# SENSOR.net
KiCad netlist of a schematic drawn in Altium Designer
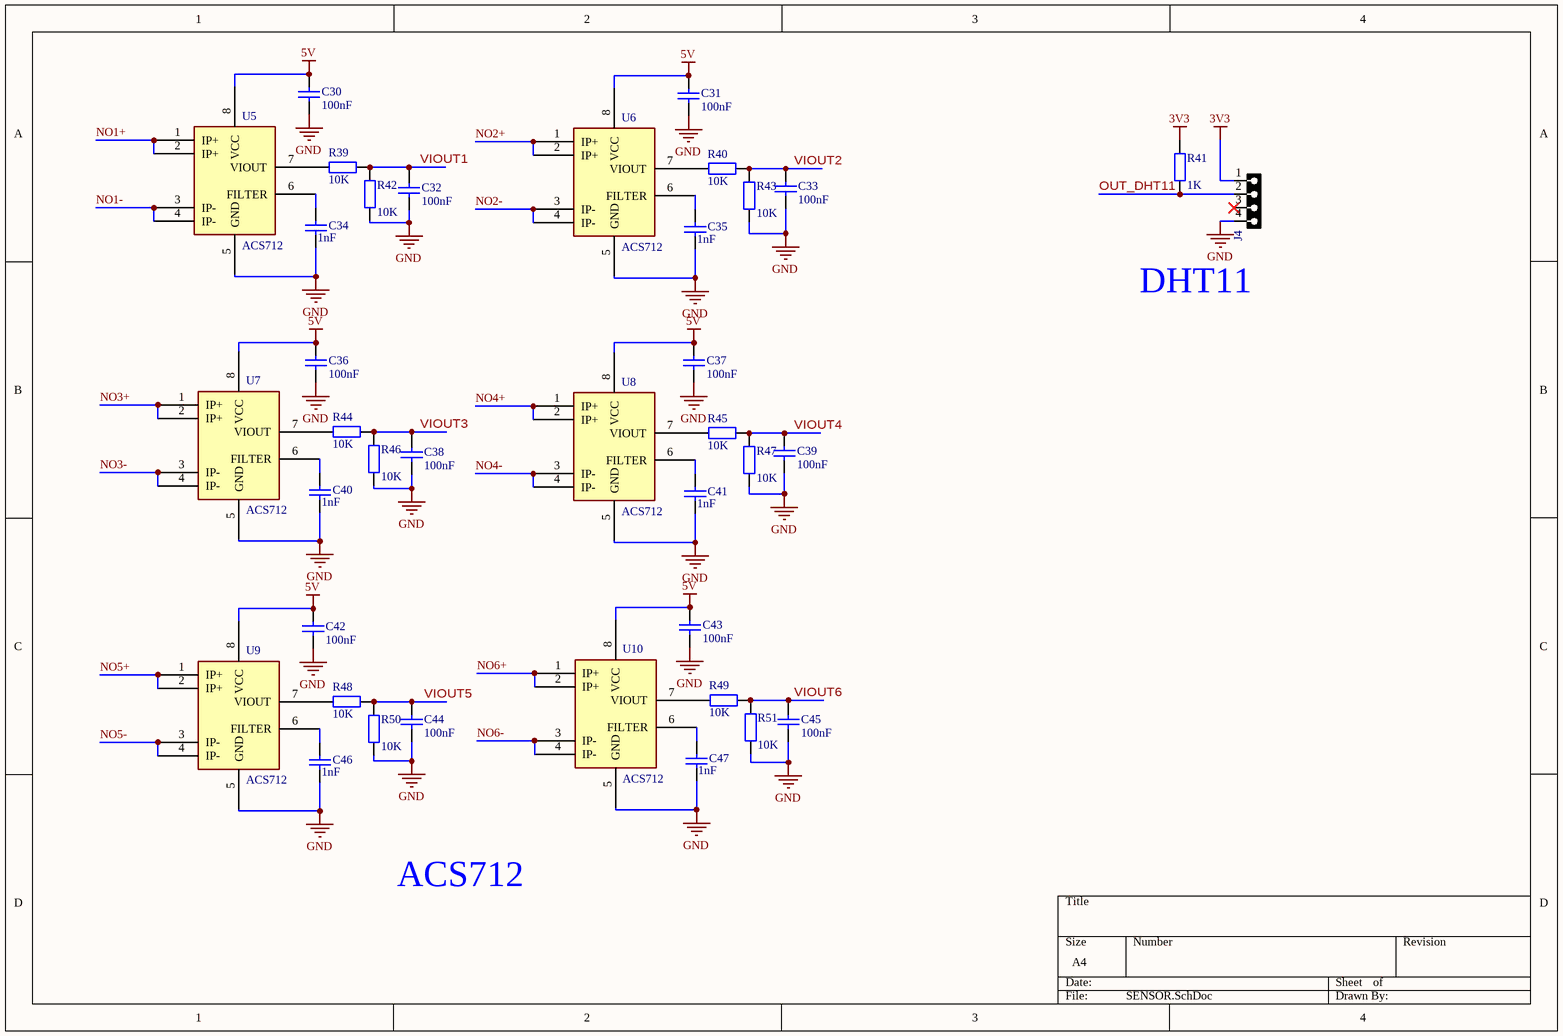
[diagram p0: SENSOR.SchDoc]

(export (version "E")
  (design (tool "Eeschema 10.0.6"))
  (components
    (comp (ref "C30")
      (value "100nF_0603_1%")
      (footprint "tu 0603")
      (description "Capacitor, Ceramic, 50V")
      (fields (field (name "MA_HANG") "100nF"))
      (libsource (lib "THU VIEN SCH") (part "Tu 0603 470pF 50V 10%"))
    )
    (comp (ref "C31")
      (value "100nF_0603_1%")
      (footprint "tu 0603")
      (description "Capacitor, Ceramic, 50V")
      (fields (field (name "MA_HANG") "100nF"))
      (libsource (lib "THU VIEN SCH") (part "Tu 0603 470pF 50V 10%"))
    )
    (comp (ref "C32")
      (value "100nF_0603_1%")
      (footprint "tu 0603")
      (description "Capacitor, Ceramic, 50V")
      (fields (field (name "MA_HANG") "100nF"))
      (libsource (lib "THU VIEN SCH") (part "Tu 0603 470pF 50V 10%"))
    )
    (comp (ref "C33")
      (value "100nF_0603_1%")
      (footprint "tu 0603")
      (description "Capacitor, Ceramic, 50V")
      (fields (field (name "MA_HANG") "100nF"))
      (libsource (lib "THU VIEN SCH") (part "Tu 0603 470pF 50V 10%"))
    )
    (comp (ref "C34")
      (value "1nF_0603_1%")
      (footprint "tu 0603")
      (description "Capacitor, Ceramic, 50V")
      (fields (field (name "MA_HANG") "1nF"))
      (libsource (lib "THU VIEN SCH") (part "Tu 0603 470pF 50V 10%"))
    )
    (comp (ref "C35")
      (value "1nF_0603_1%")
      (footprint "tu 0603")
      (description "Capacitor, Ceramic, 50V")
      (fields (field (name "MA_HANG") "1nF"))
      (libsource (lib "THU VIEN SCH") (part "Tu 0603 470pF 50V 10%"))
    )
    (comp (ref "C36")
      (value "100nF_0603_1%")
      (footprint "tu 0603")
      (description "Capacitor, Ceramic, 50V")
      (fields (field (name "MA_HANG") "100nF"))
      (libsource (lib "THU VIEN SCH") (part "Tu 0603 470pF 50V 10%"))
    )
    (comp (ref "C37")
      (value "100nF_0603_1%")
      (footprint "tu 0603")
      (description "Capacitor, Ceramic, 50V")
      (fields (field (name "MA_HANG") "100nF"))
      (libsource (lib "THU VIEN SCH") (part "Tu 0603 470pF 50V 10%"))
    )
    (comp (ref "C38")
      (value "100nF_0603_1%")
      (footprint "tu 0603")
      (description "Capacitor, Ceramic, 50V")
      (fields (field (name "MA_HANG") "100nF"))
      (libsource (lib "THU VIEN SCH") (part "Tu 0603 470pF 50V 10%"))
    )
    (comp (ref "C39")
      (value "100nF_0603_1%")
      (footprint "tu 0603")
      (description "Capacitor, Ceramic, 50V")
      (fields (field (name "MA_HANG") "100nF"))
      (libsource (lib "THU VIEN SCH") (part "Tu 0603 470pF 50V 10%"))
    )
    (comp (ref "C40")
      (value "1nF_0603_1%")
      (footprint "tu 0603")
      (description "Capacitor, Ceramic, 50V")
      (fields (field (name "MA_HANG") "1nF"))
      (libsource (lib "THU VIEN SCH") (part "Tu 0603 470pF 50V 10%"))
    )
    (comp (ref "C41")
      (value "1nF_0603_1%")
      (footprint "tu 0603")
      (description "Capacitor, Ceramic, 50V")
      (fields (field (name "MA_HANG") "1nF"))
      (libsource (lib "THU VIEN SCH") (part "Tu 0603 470pF 50V 10%"))
    )
    (comp (ref "C42")
      (value "100nF_0603_1%")
      (footprint "tu 0603")
      (description "Capacitor, Ceramic, 50V")
      (fields (field (name "MA_HANG") "100nF"))
      (libsource (lib "THU VIEN SCH") (part "Tu 0603 470pF 50V 10%"))
    )
    (comp (ref "C43")
      (value "100nF_0603_1%")
      (footprint "tu 0603")
      (description "Capacitor, Ceramic, 50V")
      (fields (field (name "MA_HANG") "100nF"))
      (libsource (lib "THU VIEN SCH") (part "Tu 0603 470pF 50V 10%"))
    )
    (comp (ref "C44")
      (value "100nF_0603_1%")
      (footprint "tu 0603")
      (description "Capacitor, Ceramic, 50V")
      (fields (field (name "MA_HANG") "100nF"))
      (libsource (lib "THU VIEN SCH") (part "Tu 0603 470pF 50V 10%"))
    )
    (comp (ref "C45")
      (value "100nF_0603_1%")
      (footprint "tu 0603")
      (description "Capacitor, Ceramic, 50V")
      (fields (field (name "MA_HANG") "100nF"))
      (libsource (lib "THU VIEN SCH") (part "Tu 0603 470pF 50V 10%"))
    )
    (comp (ref "C46")
      (value "1nF_0603_1%")
      (footprint "tu 0603")
      (description "Capacitor, Ceramic, 50V")
      (fields (field (name "MA_HANG") "1nF"))
      (libsource (lib "THU VIEN SCH") (part "Tu 0603 470pF 50V 10%"))
    )
    (comp (ref "C47")
      (value "1nF_0603_1%")
      (footprint "tu 0603")
      (description "Capacitor, Ceramic, 50V")
      (fields (field (name "MA_HANG") "1nF"))
      (libsource (lib "THU VIEN SCH") (part "Tu 0603 470pF 50V 10%"))
    )
    (comp (ref "J4")
      (value "HDRF4")
      (footprint "HDR_F_1X4")
      (description "CONN, HEADER, Female, pitch: 2.54mm, 4POS")
      (libsource (lib "AH_Library") (part "HDR_F_1X4"))
    )
    (comp (ref "R39")
      (value "10K_0603_1%")
      (footprint "tro smd 0603")
      (description "RES SMD 0603")
      (fields (field (name "MA_HANG") "10K"))
      (libsource (lib "THU VIEN SCH") (part "Tro 0603 5% 10k"))
    )
    (comp (ref "R40")
      (value "10K_0603_1%")
      (footprint "tro smd 0603")
      (description "RES SMD 0603")
      (fields (field (name "MA_HANG") "10K"))
      (libsource (lib "THU VIEN SCH") (part "Tro 0603 5% 10k"))
    )
    (comp (ref "R41")
      (value "1K_0603_1%")
      (footprint "tro smd 0603")
      (description "RES SMD 0603")
      (fields (field (name "MA_HANG") "1K"))
      (libsource (lib "THU VIEN SCH") (part "Tro 0603 5% 10k"))
    )
    (comp (ref "R42")
      (value "10K_0603_1%")
      (footprint "tro smd 0603")
      (description "RES SMD 0603")
      (fields (field (name "MA_HANG") "10K"))
      (libsource (lib "THU VIEN SCH") (part "Tro 0603 5% 10k"))
    )
    (comp (ref "R43")
      (value "10K_0603_1%")
      (footprint "tro smd 0603")
      (description "RES SMD 0603")
      (fields (field (name "MA_HANG") "10K"))
      (libsource (lib "THU VIEN SCH") (part "Tro 0603 5% 10k"))
    )
    (comp (ref "R44")
      (value "10K_0603_1%")
      (footprint "tro smd 0603")
      (description "RES SMD 0603")
      (fields (field (name "MA_HANG") "10K"))
      (libsource (lib "THU VIEN SCH") (part "Tro 0603 5% 10k"))
    )
    (comp (ref "R45")
      (value "10K_0603_1%")
      (footprint "tro smd 0603")
      (description "RES SMD 0603")
      (fields (field (name "MA_HANG") "10K"))
      (libsource (lib "THU VIEN SCH") (part "Tro 0603 5% 10k"))
    )
    (comp (ref "R46")
      (value "10K_0603_1%")
      (footprint "tro smd 0603")
      (description "RES SMD 0603")
      (fields (field (name "MA_HANG") "10K"))
      (libsource (lib "THU VIEN SCH") (part "Tro 0603 5% 10k"))
    )
    (comp (ref "R47")
      (value "10K_0603_1%")
      (footprint "tro smd 0603")
      (description "RES SMD 0603")
      (fields (field (name "MA_HANG") "10K"))
      (libsource (lib "THU VIEN SCH") (part "Tro 0603 5% 10k"))
    )
    (comp (ref "R48")
      (value "10K_0603_1%")
      (footprint "tro smd 0603")
      (description "RES SMD 0603")
      (fields (field (name "MA_HANG") "10K"))
      (libsource (lib "THU VIEN SCH") (part "Tro 0603 5% 10k"))
    )
    (comp (ref "R49")
      (value "10K_0603_1%")
      (footprint "tro smd 0603")
      (description "RES SMD 0603")
      (fields (field (name "MA_HANG") "10K"))
      (libsource (lib "THU VIEN SCH") (part "Tro 0603 5% 10k"))
    )
    (comp (ref "R50")
      (value "10K_0603_1%")
      (footprint "tro smd 0603")
      (description "RES SMD 0603")
      (fields (field (name "MA_HANG") "10K"))
      (libsource (lib "THU VIEN SCH") (part "Tro 0603 5% 10k"))
    )
    (comp (ref "R51")
      (value "10K_0603_1%")
      (footprint "tro smd 0603")
      (description "RES SMD 0603")
      (fields (field (name "MA_HANG") "10K"))
      (libsource (lib "THU VIEN SCH") (part "Tro 0603 5% 10k"))
    )
    (comp (ref "U5")
      (value "ACS712")
      (footprint "SO_8")
      (description "IC, CURRENT SENSOR, HALL EFFECT")
      (fields (field (name "MANF") "Allegro") (field (name "Comment") "ACS712_8SOIC"))
      (libsource (lib "AH_Library") (part "ACS712"))
    )
    (comp (ref "U6")
      (value "ACS712")
      (footprint "SO_8")
      (description "IC, CURRENT SENSOR, HALL EFFECT")
      (fields (field (name "MANF") "Allegro") (field (name "Comment") "ACS712_8SOIC"))
      (libsource (lib "AH_Library") (part "ACS712"))
    )
    (comp (ref "U7")
      (value "ACS712")
      (footprint "SO_8")
      (description "IC, CURRENT SENSOR, HALL EFFECT")
      (fields (field (name "MANF") "Allegro") (field (name "Comment") "ACS712_8SOIC"))
      (libsource (lib "AH_Library") (part "ACS712"))
    )
    (comp (ref "U8")
      (value "ACS712")
      (footprint "SO_8")
      (description "IC, CURRENT SENSOR, HALL EFFECT")
      (fields (field (name "MANF") "Allegro") (field (name "Comment") "ACS712_8SOIC"))
      (libsource (lib "AH_Library") (part "ACS712"))
    )
    (comp (ref "U9")
      (value "ACS712")
      (footprint "SO_8")
      (description "IC, CURRENT SENSOR, HALL EFFECT")
      (fields (field (name "MANF") "Allegro") (field (name "Comment") "ACS712_8SOIC"))
      (libsource (lib "AH_Library") (part "ACS712"))
    )
    (comp (ref "U10")
      (value "ACS712")
      (footprint "SO_8")
      (description "IC, CURRENT SENSOR, HALL EFFECT")
      (fields (field (name "MANF") "Allegro") (field (name "Comment") "ACS712_8SOIC"))
      (libsource (lib "AH_Library") (part "ACS712"))
    )
  )
  (nets
    (net (code "1") (name "/NO1+") (class "Default")
      (node (ref "U5") (pin "1") (pinfunction "IP+_1") (pintype "passive"))
      (node (ref "U5") (pin "2") (pinfunction "IP+_2") (pintype "passive"))
    )
    (net (code "2") (name "/NO1-") (class "Default")
      (node (ref "U5") (pin "3") (pinfunction "IP-_3") (pintype "passive"))
      (node (ref "U5") (pin "4") (pinfunction "IP-_4") (pintype "passive"))
    )
    (net (code "3") (name "/NO2+") (class "Default")
      (node (ref "U6") (pin "1") (pinfunction "IP+_1") (pintype "passive"))
      (node (ref "U6") (pin "2") (pinfunction "IP+_2") (pintype "passive"))
    )
    (net (code "4") (name "/NO2-") (class "Default")
      (node (ref "U6") (pin "3") (pinfunction "IP-_3") (pintype "passive"))
      (node (ref "U6") (pin "4") (pinfunction "IP-_4") (pintype "passive"))
    )
    (net (code "5") (name "/NO3+") (class "Default")
      (node (ref "U7") (pin "1") (pinfunction "IP+_1") (pintype "passive"))
      (node (ref "U7") (pin "2") (pinfunction "IP+_2") (pintype "passive"))
    )
    (net (code "6") (name "/NO3-") (class "Default")
      (node (ref "U7") (pin "3") (pinfunction "IP-_3") (pintype "passive"))
      (node (ref "U7") (pin "4") (pinfunction "IP-_4") (pintype "passive"))
    )
    (net (code "7") (name "/NO4+") (class "Default")
      (node (ref "U8") (pin "1") (pinfunction "IP+_1") (pintype "passive"))
      (node (ref "U8") (pin "2") (pinfunction "IP+_2") (pintype "passive"))
    )
    (net (code "8") (name "/NO4-") (class "Default")
      (node (ref "U8") (pin "3") (pinfunction "IP-_3") (pintype "passive"))
      (node (ref "U8") (pin "4") (pinfunction "IP-_4") (pintype "passive"))
    )
    (net (code "9") (name "/NO5+") (class "Default")
      (node (ref "U9") (pin "1") (pinfunction "IP+_1") (pintype "passive"))
      (node (ref "U9") (pin "2") (pinfunction "IP+_2") (pintype "passive"))
    )
    (net (code "10") (name "/NO5-") (class "Default")
      (node (ref "U9") (pin "3") (pinfunction "IP-_3") (pintype "passive"))
      (node (ref "U9") (pin "4") (pinfunction "IP-_4") (pintype "passive"))
    )
    (net (code "11") (name "/NO6+") (class "Default")
      (node (ref "U10") (pin "1") (pinfunction "IP+_1") (pintype "passive"))
      (node (ref "U10") (pin "2") (pinfunction "IP+_2") (pintype "passive"))
    )
    (net (code "12") (name "/NO6-") (class "Default")
      (node (ref "U10") (pin "3") (pinfunction "IP-_3") (pintype "passive"))
      (node (ref "U10") (pin "4") (pinfunction "IP-_4") (pintype "passive"))
    )
    (net (code "13") (name "/OUT_DHT11") (class "Default")
      (node (ref "J4") (pin "2") (pinfunction "2_2") (pintype "passive"))
      (node (ref "R41") (pin "1") (pinfunction "1_1") (pintype "passive"))
    )
    (net (code "14") (name "/VIOUT1") (class "Default")
      (node (ref "C32") (pin "1") (pinfunction "1_1") (pintype "passive"))
      (node (ref "R39") (pin "1") (pinfunction "1_1") (pintype "passive"))
      (node (ref "R42") (pin "2") (pinfunction "2_2") (pintype "passive"))
    )
    (net (code "15") (name "/VIOUT2") (class "Default")
      (node (ref "C33") (pin "1") (pinfunction "1_1") (pintype "passive"))
      (node (ref "R40") (pin "1") (pinfunction "1_1") (pintype "passive"))
      (node (ref "R43") (pin "2") (pinfunction "2_2") (pintype "passive"))
    )
    (net (code "16") (name "/VIOUT3") (class "Default")
      (node (ref "C38") (pin "1") (pinfunction "1_1") (pintype "passive"))
      (node (ref "R44") (pin "1") (pinfunction "1_1") (pintype "passive"))
      (node (ref "R46") (pin "2") (pinfunction "2_2") (pintype "passive"))
    )
    (net (code "17") (name "/VIOUT4") (class "Default")
      (node (ref "C39") (pin "1") (pinfunction "1_1") (pintype "passive"))
      (node (ref "R45") (pin "1") (pinfunction "1_1") (pintype "passive"))
      (node (ref "R47") (pin "2") (pinfunction "2_2") (pintype "passive"))
    )
    (net (code "18") (name "/VIOUT5") (class "Default")
      (node (ref "C44") (pin "1") (pinfunction "1_1") (pintype "passive"))
      (node (ref "R48") (pin "1") (pinfunction "1_1") (pintype "passive"))
      (node (ref "R50") (pin "2") (pinfunction "2_2") (pintype "passive"))
    )
    (net (code "19") (name "/VIOUT6") (class "Default")
      (node (ref "C45") (pin "1") (pinfunction "1_1") (pintype "passive"))
      (node (ref "R49") (pin "1") (pinfunction "1_1") (pintype "passive"))
      (node (ref "R51") (pin "2") (pinfunction "2_2") (pintype "passive"))
    )
    (net (code "20") (name "3V3") (class "Default")
      (node (ref "J4") (pin "1") (pinfunction "1_1") (pintype "passive"))
      (node (ref "R41") (pin "2") (pinfunction "2_2") (pintype "passive"))
    )
    (net (code "21") (name "5V") (class "Default")
      (node (ref "C30") (pin "1") (pinfunction "1_1") (pintype "passive"))
      (node (ref "C31") (pin "1") (pinfunction "1_1") (pintype "passive"))
      (node (ref "C36") (pin "1") (pinfunction "1_1") (pintype "passive"))
      (node (ref "C37") (pin "1") (pinfunction "1_1") (pintype "passive"))
      (node (ref "C42") (pin "1") (pinfunction "1_1") (pintype "passive"))
      (node (ref "C43") (pin "1") (pinfunction "1_1") (pintype "passive"))
      (node (ref "U10") (pin "8") (pinfunction "VCC_8") (pintype "passive"))
      (node (ref "U5") (pin "8") (pinfunction "VCC_8") (pintype "passive"))
      (node (ref "U6") (pin "8") (pinfunction "VCC_8") (pintype "passive"))
      (node (ref "U7") (pin "8") (pinfunction "VCC_8") (pintype "passive"))
      (node (ref "U8") (pin "8") (pinfunction "VCC_8") (pintype "passive"))
      (node (ref "U9") (pin "8") (pinfunction "VCC_8") (pintype "passive"))
    )
    (net (code "22") (name "GND") (class "Default")
      (node (ref "C30") (pin "2") (pinfunction "2_2") (pintype "passive"))
      (node (ref "C31") (pin "2") (pinfunction "2_2") (pintype "passive"))
      (node (ref "C32") (pin "2") (pinfunction "2_2") (pintype "passive"))
      (node (ref "C33") (pin "2") (pinfunction "2_2") (pintype "passive"))
      (node (ref "C34") (pin "2") (pinfunction "2_2") (pintype "passive"))
      (node (ref "C35") (pin "2") (pinfunction "2_2") (pintype "passive"))
      (node (ref "C36") (pin "2") (pinfunction "2_2") (pintype "passive"))
      (node (ref "C37") (pin "2") (pinfunction "2_2") (pintype "passive"))
      (node (ref "C38") (pin "2") (pinfunction "2_2") (pintype "passive"))
      (node (ref "C39") (pin "2") (pinfunction "2_2") (pintype "passive"))
      (node (ref "C40") (pin "2") (pinfunction "2_2") (pintype "passive"))
      (node (ref "C41") (pin "2") (pinfunction "2_2") (pintype "passive"))
      (node (ref "C42") (pin "2") (pinfunction "2_2") (pintype "passive"))
      (node (ref "C43") (pin "2") (pinfunction "2_2") (pintype "passive"))
      (node (ref "C44") (pin "2") (pinfunction "2_2") (pintype "passive"))
      (node (ref "C45") (pin "2") (pinfunction "2_2") (pintype "passive"))
      (node (ref "C46") (pin "2") (pinfunction "2_2") (pintype "passive"))
      (node (ref "C47") (pin "2") (pinfunction "2_2") (pintype "passive"))
      (node (ref "J4") (pin "4") (pinfunction "4_4") (pintype "passive"))
      (node (ref "R42") (pin "1") (pinfunction "1_1") (pintype "passive"))
      (node (ref "R43") (pin "1") (pinfunction "1_1") (pintype "passive"))
      (node (ref "R46") (pin "1") (pinfunction "1_1") (pintype "passive"))
      (node (ref "R47") (pin "1") (pinfunction "1_1") (pintype "passive"))
      (node (ref "R50") (pin "1") (pinfunction "1_1") (pintype "passive"))
      (node (ref "R51") (pin "1") (pinfunction "1_1") (pintype "passive"))
      (node (ref "U10") (pin "5") (pinfunction "GND_5") (pintype "passive"))
      (node (ref "U5") (pin "5") (pinfunction "GND_5") (pintype "passive"))
      (node (ref "U6") (pin "5") (pinfunction "GND_5") (pintype "passive"))
      (node (ref "U7") (pin "5") (pinfunction "GND_5") (pintype "passive"))
      (node (ref "U8") (pin "5") (pinfunction "GND_5") (pintype "passive"))
      (node (ref "U9") (pin "5") (pinfunction "GND_5") (pintype "passive"))
    )
    (net (code "23") (name "Net-(U5-FILTER)") (class "Default")
      (node (ref "C34") (pin "1") (pinfunction "1_1") (pintype "passive"))
      (node (ref "U5") (pin "6") (pinfunction "FILTER_6") (pintype "passive"))
    )
    (net (code "24") (name "Net-(U5-VIOUT)") (class "Default")
      (node (ref "R39") (pin "2") (pinfunction "2_2") (pintype "passive"))
      (node (ref "U5") (pin "7") (pinfunction "VIOUT_7") (pintype "passive"))
    )
    (net (code "25") (name "Net-(U6-FILTER)") (class "Default")
      (node (ref "C35") (pin "1") (pinfunction "1_1") (pintype "passive"))
      (node (ref "U6") (pin "6") (pinfunction "FILTER_6") (pintype "passive"))
    )
    (net (code "26") (name "Net-(U6-VIOUT)") (class "Default")
      (node (ref "R40") (pin "2") (pinfunction "2_2") (pintype "passive"))
      (node (ref "U6") (pin "7") (pinfunction "VIOUT_7") (pintype "passive"))
    )
    (net (code "27") (name "Net-(U7-FILTER)") (class "Default")
      (node (ref "C40") (pin "1") (pinfunction "1_1") (pintype "passive"))
      (node (ref "U7") (pin "6") (pinfunction "FILTER_6") (pintype "passive"))
    )
    (net (code "28") (name "Net-(U7-VIOUT)") (class "Default")
      (node (ref "R44") (pin "2") (pinfunction "2_2") (pintype "passive"))
      (node (ref "U7") (pin "7") (pinfunction "VIOUT_7") (pintype "passive"))
    )
    (net (code "29") (name "Net-(U8-FILTER)") (class "Default")
      (node (ref "C41") (pin "1") (pinfunction "1_1") (pintype "passive"))
      (node (ref "U8") (pin "6") (pinfunction "FILTER_6") (pintype "passive"))
    )
    (net (code "30") (name "Net-(U8-VIOUT)") (class "Default")
      (node (ref "R45") (pin "2") (pinfunction "2_2") (pintype "passive"))
      (node (ref "U8") (pin "7") (pinfunction "VIOUT_7") (pintype "passive"))
    )
    (net (code "31") (name "Net-(U9-FILTER)") (class "Default")
      (node (ref "C46") (pin "1") (pinfunction "1_1") (pintype "passive"))
      (node (ref "U9") (pin "6") (pinfunction "FILTER_6") (pintype "passive"))
    )
    (net (code "32") (name "Net-(U9-VIOUT)") (class "Default")
      (node (ref "R48") (pin "2") (pinfunction "2_2") (pintype "passive"))
      (node (ref "U9") (pin "7") (pinfunction "VIOUT_7") (pintype "passive"))
    )
    (net (code "33") (name "Net-(U10-FILTER)") (class "Default")
      (node (ref "C47") (pin "1") (pinfunction "1_1") (pintype "passive"))
      (node (ref "U10") (pin "6") (pinfunction "FILTER_6") (pintype "passive"))
    )
    (net (code "34") (name "Net-(U10-VIOUT)") (class "Default")
      (node (ref "R49") (pin "2") (pinfunction "2_2") (pintype "passive"))
      (node (ref "U10") (pin "7") (pinfunction "VIOUT_7") (pintype "passive"))
    )
    (net (code "35") (name "unconnected-(J4-Pad3)") (class "Default")
      (node (ref "J4") (pin "3") (pinfunction "3_3") (pintype "passive+no_connect"))
    )
  )
)
